# ESPHome_4-switch.net
KiCad netlist of a schematic drawn in EAGLE
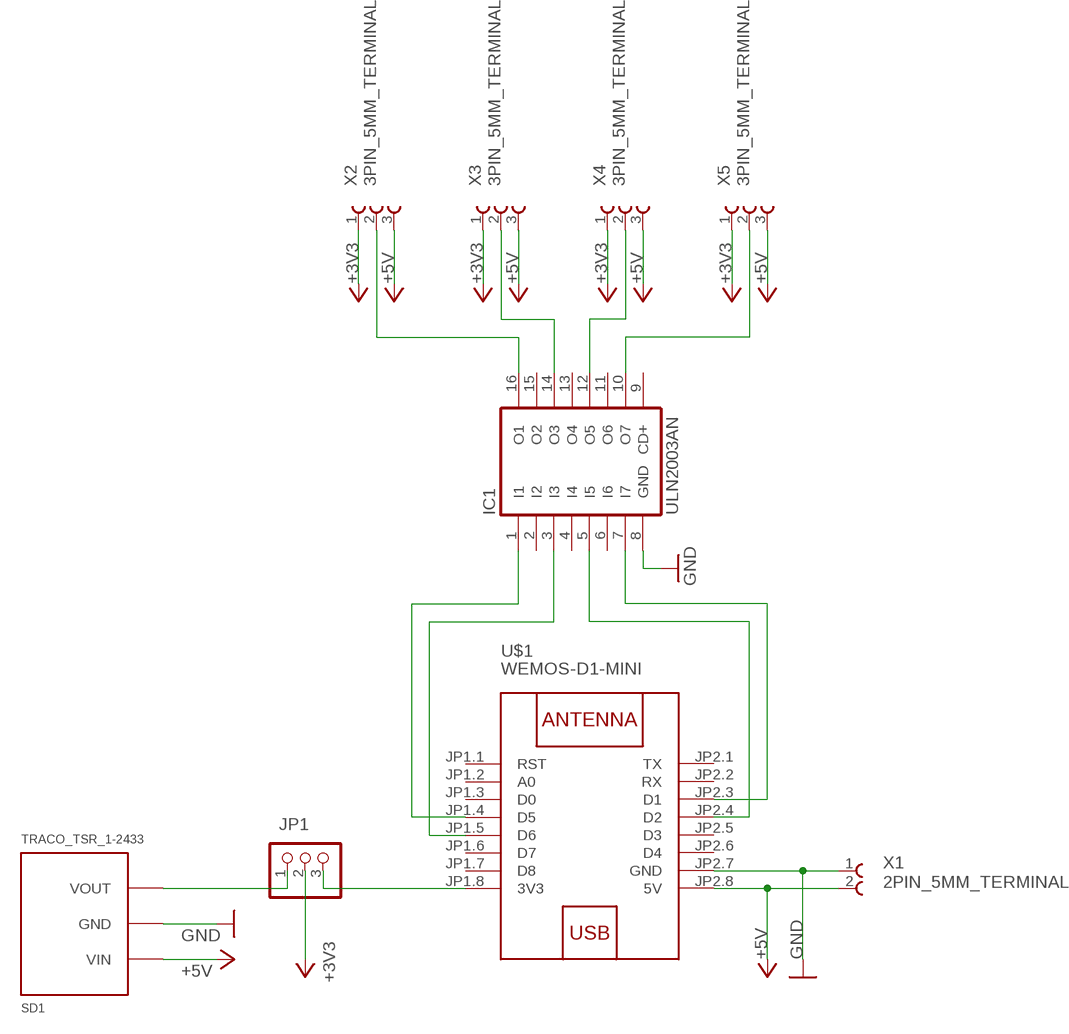
[diagram p0: schematic, sheet 1]

(export (version "E")
  (design (tool "Eeschema 10.0.6"))
  (components
    (comp (ref "IC1")
      (value "ULN2003AN")
      (footprint "eagle-import:DIL16")
      (libsource (lib "eagle-import") (part "ULN2003AN"))
    )
    (comp (ref "JP1")
      (value "PINHD-1X3")
      (footprint "eagle-import:1X03")
      (libsource (lib "eagle-import") (part "PINHD-1X3"))
    )
    (comp (ref "SD1")
      (value "TRACO_TSR_1-2433")
      (footprint "eagle-import:TRACO_TSR_1-24XX")
      (libsource (lib "eagle-import") (part "TRACO_TSR_1-2433"))
    )
    (comp (ref "U$1")
      (value "WEMOS-D1-MINI")
      (footprint "eagle-import:WEMOS-D1-MINI")
      (libsource (lib "eagle-import") (part "WEMOS-D1-MINI"))
    )
    (comp (ref "X1")
      (value "2PIN_5MM_TERMINAL")
      (footprint "eagle-import:2PIN_5MM_TERMMINAL")
      (libsource (lib "eagle-import") (part "2PIN_5MM_TERMINAL"))
    )
    (comp (ref "X2")
      (value "3PIN_5MM_TERMINAL")
      (footprint "eagle-import:3PIN_5MM_TERMINAL")
      (libsource (lib "eagle-import") (part "3PIN_5MM_TERMINAL"))
    )
    (comp (ref "X3")
      (value "3PIN_5MM_TERMINAL")
      (footprint "eagle-import:3PIN_5MM_TERMINAL")
      (libsource (lib "eagle-import") (part "3PIN_5MM_TERMINAL"))
    )
    (comp (ref "X4")
      (value "3PIN_5MM_TERMINAL")
      (footprint "eagle-import:3PIN_5MM_TERMINAL")
      (libsource (lib "eagle-import") (part "3PIN_5MM_TERMINAL"))
    )
    (comp (ref "X5")
      (value "3PIN_5MM_TERMINAL")
      (footprint "eagle-import:3PIN_5MM_TERMINAL")
      (libsource (lib "eagle-import") (part "3PIN_5MM_TERMINAL"))
    )
  )
  (nets
    (net (code "1") (name "+3V3") (class "Default")
      (node (ref "JP1") (pin "2") (pinfunction "2_2") (pintype "passive"))
      (node (ref "X2") (pin "1") (pinfunction "1_1") (pintype "passive"))
      (node (ref "X3") (pin "1") (pinfunction "1_1") (pintype "passive"))
      (node (ref "X4") (pin "1") (pinfunction "1_1") (pintype "passive"))
      (node (ref "X5") (pin "1") (pinfunction "1_1") (pintype "passive"))
    )
    (net (code "2") (name "+5V") (class "Default")
      (node (ref "SD1") (pin "VIN") (pinfunction "VIN_VIN") (pintype "input"))
      (node (ref "U$1") (pin "JP2.8") (pinfunction "5V_JP2.8") (pintype "power_in"))
      (node (ref "X1") (pin "2") (pinfunction "2_2") (pintype "passive"))
      (node (ref "X2") (pin "3") (pinfunction "3_3") (pintype "passive"))
      (node (ref "X3") (pin "3") (pinfunction "3_3") (pintype "passive"))
      (node (ref "X4") (pin "3") (pinfunction "3_3") (pintype "passive"))
      (node (ref "X5") (pin "3") (pinfunction "3_3") (pintype "passive"))
    )
    (net (code "3") (name "GND") (class "Default")
      (node (ref "IC1") (pin "8") (pinfunction "GND_8") (pintype "power_in"))
      (node (ref "SD1") (pin "GND") (pinfunction "GND_GND") (pintype "bidirectional"))
      (node (ref "U$1") (pin "JP2.7") (pinfunction "GND_JP2.7") (pintype "power_in"))
      (node (ref "X1") (pin "1") (pinfunction "1_1") (pintype "passive"))
    )
    (net (code "4") (name "Net-(IC1-I1)") (class "Default")
      (node (ref "IC1") (pin "1") (pinfunction "I1_1") (pintype "input"))
      (node (ref "U$1") (pin "JP1.4") (pinfunction "D5_JP1.4") (pintype "bidirectional"))
    )
    (net (code "5") (name "Net-(IC1-I3)") (class "Default")
      (node (ref "IC1") (pin "3") (pinfunction "I3_3") (pintype "input"))
      (node (ref "U$1") (pin "JP1.5") (pinfunction "D6_JP1.5") (pintype "bidirectional"))
    )
    (net (code "6") (name "Net-(IC1-I5)") (class "Default")
      (node (ref "IC1") (pin "5") (pinfunction "I5_5") (pintype "input"))
      (node (ref "U$1") (pin "JP2.4") (pinfunction "D2_JP2.4") (pintype "bidirectional"))
    )
    (net (code "7") (name "Net-(IC1-I7)") (class "Default")
      (node (ref "IC1") (pin "7") (pinfunction "I7_7") (pintype "input"))
      (node (ref "U$1") (pin "JP2.3") (pinfunction "D1_JP2.3") (pintype "bidirectional"))
    )
    (net (code "8") (name "Net-(IC1-O1)") (class "Default")
      (node (ref "IC1") (pin "16") (pinfunction "O1_16") (pintype "open_collector"))
      (node (ref "X2") (pin "2") (pinfunction "2_2") (pintype "passive"))
    )
    (net (code "9") (name "Net-(IC1-O3)") (class "Default")
      (node (ref "IC1") (pin "14") (pinfunction "O3_14") (pintype "open_collector"))
      (node (ref "X3") (pin "2") (pinfunction "2_2") (pintype "passive"))
    )
    (net (code "10") (name "Net-(IC1-O5)") (class "Default")
      (node (ref "IC1") (pin "12") (pinfunction "O5_12") (pintype "open_collector"))
      (node (ref "X4") (pin "2") (pinfunction "2_2") (pintype "passive"))
    )
    (net (code "11") (name "Net-(IC1-O7)") (class "Default")
      (node (ref "IC1") (pin "10") (pinfunction "O7_10") (pintype "open_collector"))
      (node (ref "X5") (pin "2") (pinfunction "2_2") (pintype "passive"))
    )
    (net (code "12") (name "Net-(JP1-Pad1)") (class "Default")
      (node (ref "JP1") (pin "1") (pinfunction "1_1") (pintype "passive"))
      (node (ref "SD1") (pin "VOUT") (pinfunction "VOUT_VOUT") (pintype "output"))
    )
    (net (code "13") (name "Net-(U$1-3V3)") (class "Default")
      (node (ref "JP1") (pin "3") (pinfunction "3_3") (pintype "passive"))
      (node (ref "U$1") (pin "JP1.8") (pinfunction "3V3_JP1.8") (pintype "power_in"))
    )
    (net (code "14") (name "unconnected-(IC1-CD+-Pad9)") (class "Default")
      (node (ref "IC1") (pin "9") (pinfunction "CD+_9") (pintype "passive"))
    )
    (net (code "15") (name "unconnected-(IC1-I2-Pad2)") (class "Default")
      (node (ref "IC1") (pin "2") (pinfunction "I2_2") (pintype "input"))
    )
    (net (code "16") (name "unconnected-(IC1-I4-Pad4)") (class "Default")
      (node (ref "IC1") (pin "4") (pinfunction "I4_4") (pintype "input"))
    )
    (net (code "17") (name "unconnected-(IC1-I6-Pad6)") (class "Default")
      (node (ref "IC1") (pin "6") (pinfunction "I6_6") (pintype "input"))
    )
    (net (code "18") (name "unconnected-(IC1-O2-Pad15)") (class "Default")
      (node (ref "IC1") (pin "15") (pinfunction "O2_15") (pintype "open_collector"))
    )
    (net (code "19") (name "unconnected-(IC1-O4-Pad13)") (class "Default")
      (node (ref "IC1") (pin "13") (pinfunction "O4_13") (pintype "open_collector"))
    )
    (net (code "20") (name "unconnected-(IC1-O6-Pad11)") (class "Default")
      (node (ref "IC1") (pin "11") (pinfunction "O6_11") (pintype "open_collector"))
    )
    (net (code "21") (name "unconnected-(U$1-A0-PadJP1.2)") (class "Default")
      (node (ref "U$1") (pin "JP1.2") (pinfunction "A0_JP1.2") (pintype "bidirectional"))
    )
    (net (code "22") (name "unconnected-(U$1-D0-PadJP1.3)") (class "Default")
      (node (ref "U$1") (pin "JP1.3") (pinfunction "D0_JP1.3") (pintype "bidirectional"))
    )
    (net (code "23") (name "unconnected-(U$1-D3-PadJP2.5)") (class "Default")
      (node (ref "U$1") (pin "JP2.5") (pinfunction "D3_JP2.5") (pintype "bidirectional"))
    )
    (net (code "24") (name "unconnected-(U$1-D4-PadJP2.6)") (class "Default")
      (node (ref "U$1") (pin "JP2.6") (pinfunction "D4_JP2.6") (pintype "bidirectional"))
    )
    (net (code "25") (name "unconnected-(U$1-D7-PadJP1.6)") (class "Default")
      (node (ref "U$1") (pin "JP1.6") (pinfunction "D7_JP1.6") (pintype "bidirectional"))
    )
    (net (code "26") (name "unconnected-(U$1-D8-PadJP1.7)") (class "Default")
      (node (ref "U$1") (pin "JP1.7") (pinfunction "D8_JP1.7") (pintype "bidirectional"))
    )
    (net (code "27") (name "unconnected-(U$1-RST-PadJP1.1)") (class "Default")
      (node (ref "U$1") (pin "JP1.1") (pinfunction "RST_JP1.1") (pintype "bidirectional"))
    )
    (net (code "28") (name "unconnected-(U$1-RX-PadJP2.2)") (class "Default")
      (node (ref "U$1") (pin "JP2.2") (pinfunction "RX_JP2.2") (pintype "bidirectional"))
    )
    (net (code "29") (name "unconnected-(U$1-TX-PadJP2.1)") (class "Default")
      (node (ref "U$1") (pin "JP2.1") (pinfunction "TX_JP2.1") (pintype "bidirectional"))
    )
  )
)
